# 00A-004.net
KiCad netlist of a schematic drawn in EAGLE
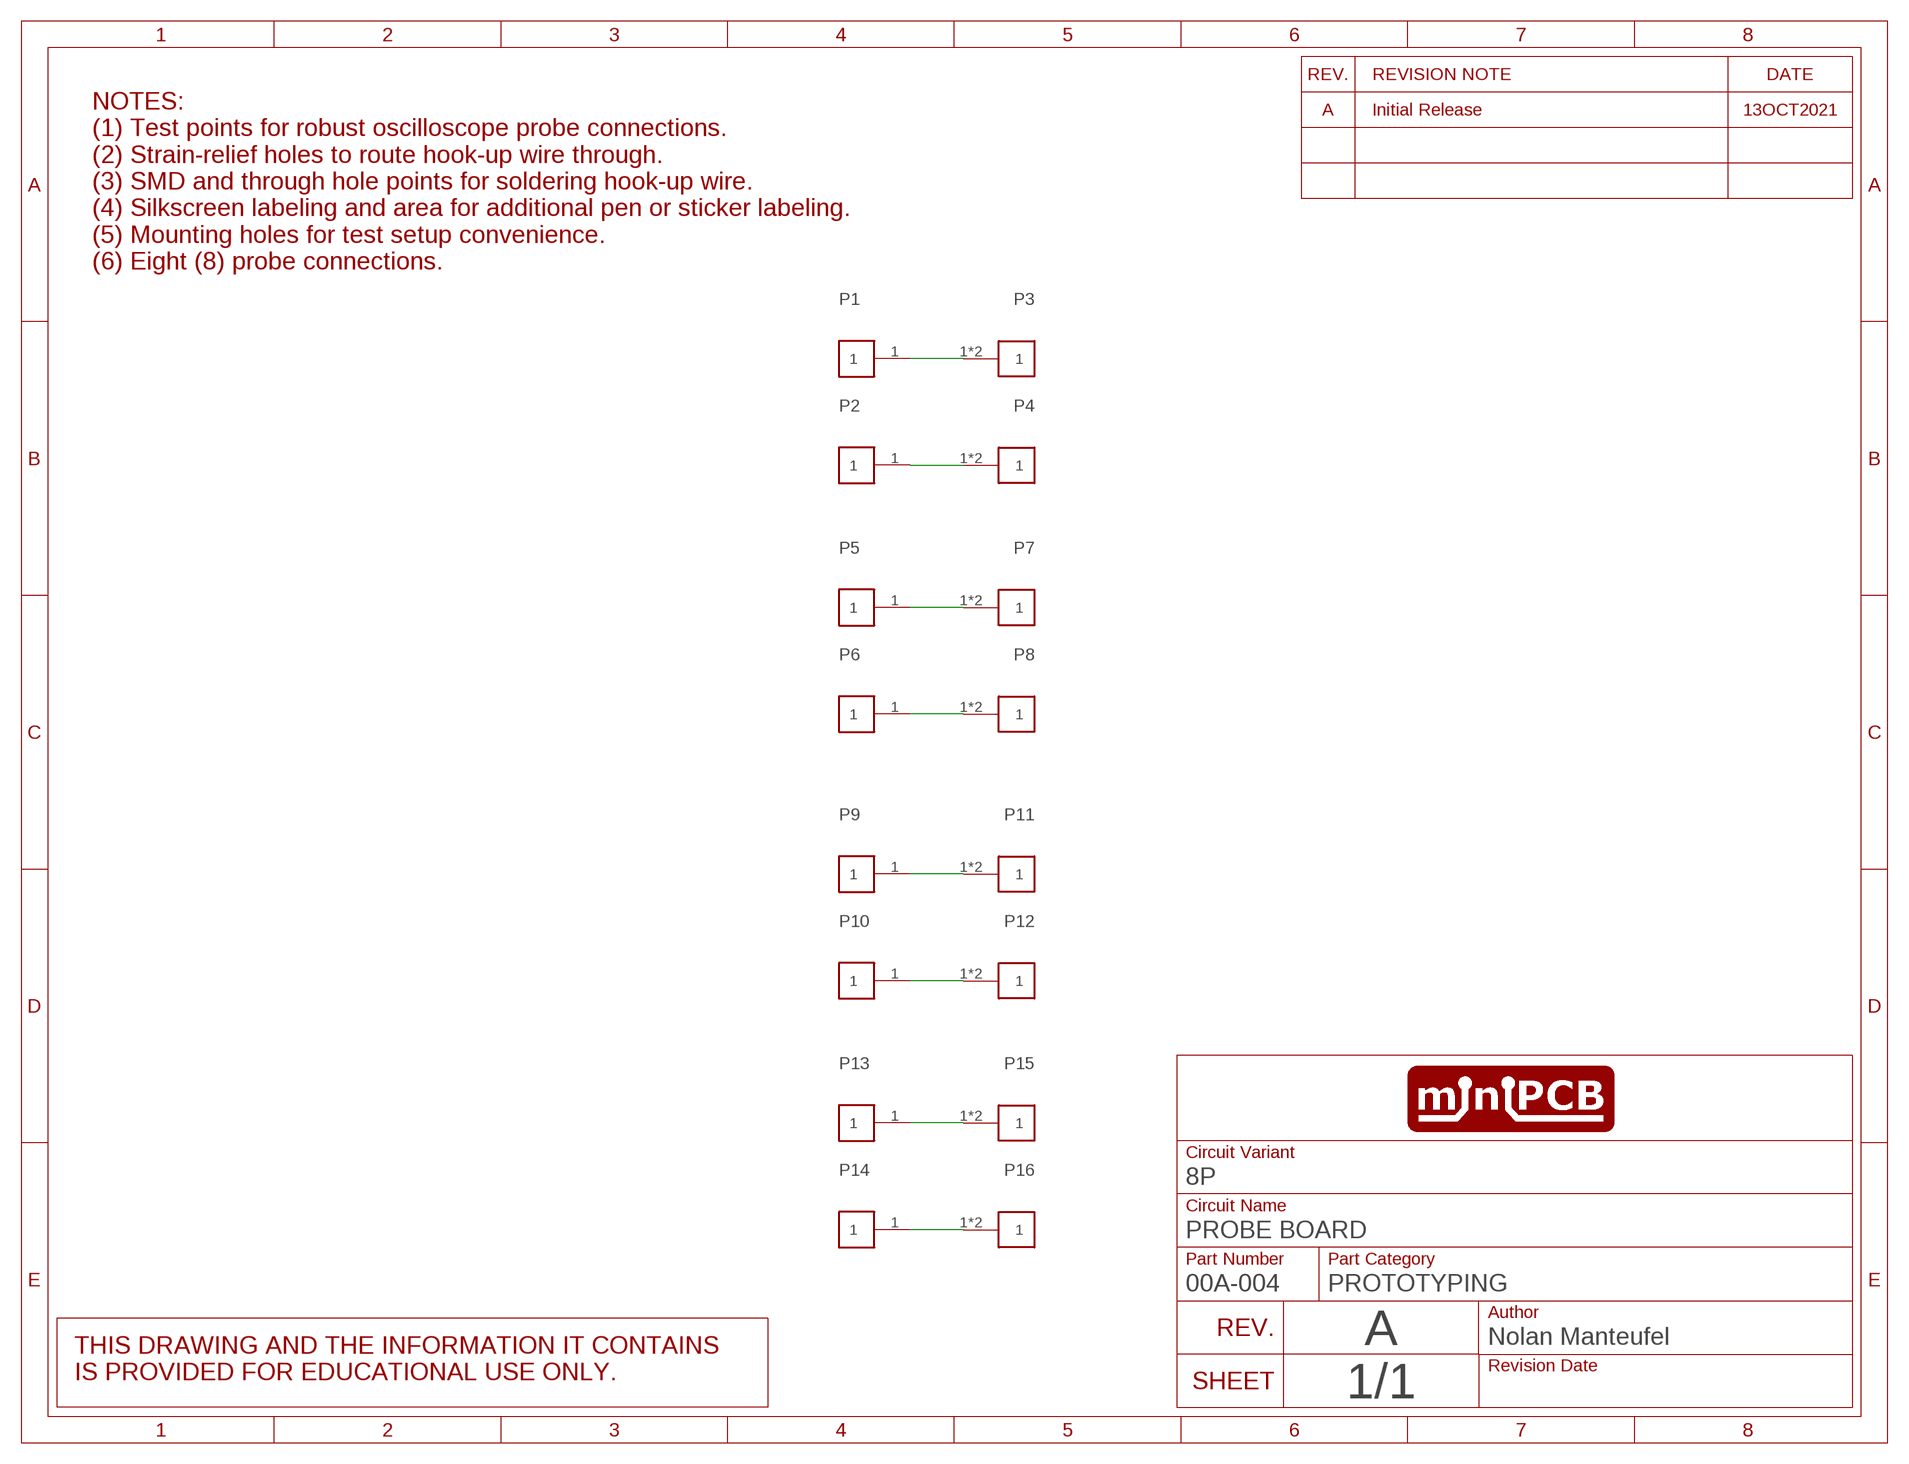
[diagram p0: schematic, sheet 1]

(export (version "E")
  (design (tool "Eeschema 10.0.6"))
  (components
    (comp (ref "P1")
      (value "PINS_1KE_5000")
      (footprint "eagle-import:PINS_1_TESTPOINT_KE5000")
      (libsource (lib "eagle-import") (part "PINS_1KE_5000"))
    )
    (comp (ref "P2")
      (value "PINS_1KE_5000")
      (footprint "eagle-import:PINS_1_TESTPOINT_KE5000")
      (libsource (lib "eagle-import") (part "PINS_1KE_5000"))
    )
    (comp (ref "P3")
      (value "PINS_124AWG")
      (footprint "eagle-import:PINS_1_1MM")
      (libsource (lib "eagle-import") (part "PINS_124AWG"))
    )
    (comp (ref "P4")
      (value "PINS_124AWG")
      (footprint "eagle-import:PINS_1_1MM")
      (libsource (lib "eagle-import") (part "PINS_124AWG"))
    )
    (comp (ref "P5")
      (value "PINS_1KE_5000")
      (footprint "eagle-import:PINS_1_TESTPOINT_KE5000")
      (libsource (lib "eagle-import") (part "PINS_1KE_5000"))
    )
    (comp (ref "P6")
      (value "PINS_1KE_5000")
      (footprint "eagle-import:PINS_1_TESTPOINT_KE5000")
      (libsource (lib "eagle-import") (part "PINS_1KE_5000"))
    )
    (comp (ref "P7")
      (value "PINS_124AWG")
      (footprint "eagle-import:PINS_1_1MM")
      (libsource (lib "eagle-import") (part "PINS_124AWG"))
    )
    (comp (ref "P8")
      (value "PINS_124AWG")
      (footprint "eagle-import:PINS_1_1MM")
      (libsource (lib "eagle-import") (part "PINS_124AWG"))
    )
    (comp (ref "P9")
      (value "PINS_1KE_5000")
      (footprint "eagle-import:PINS_1_TESTPOINT_KE5000")
      (libsource (lib "eagle-import") (part "PINS_1KE_5000"))
    )
    (comp (ref "P10")
      (value "PINS_1KE_5000")
      (footprint "eagle-import:PINS_1_TESTPOINT_KE5000")
      (libsource (lib "eagle-import") (part "PINS_1KE_5000"))
    )
    (comp (ref "P11")
      (value "PINS_124AWG")
      (footprint "eagle-import:PINS_1_1MM")
      (libsource (lib "eagle-import") (part "PINS_124AWG"))
    )
    (comp (ref "P12")
      (value "PINS_124AWG")
      (footprint "eagle-import:PINS_1_1MM")
      (libsource (lib "eagle-import") (part "PINS_124AWG"))
    )
    (comp (ref "P13")
      (value "PINS_1KE_5000")
      (footprint "eagle-import:PINS_1_TESTPOINT_KE5000")
      (libsource (lib "eagle-import") (part "PINS_1KE_5000"))
    )
    (comp (ref "P14")
      (value "PINS_1KE_5000")
      (footprint "eagle-import:PINS_1_TESTPOINT_KE5000")
      (libsource (lib "eagle-import") (part "PINS_1KE_5000"))
    )
    (comp (ref "P15")
      (value "PINS_124AWG")
      (footprint "eagle-import:PINS_1_1MM")
      (libsource (lib "eagle-import") (part "PINS_124AWG"))
    )
    (comp (ref "P16")
      (value "PINS_124AWG")
      (footprint "eagle-import:PINS_1_1MM")
      (libsource (lib "eagle-import") (part "PINS_124AWG"))
    )
  )
  (nets
    (net (code "1") (name "Net-(P1-Pad1)") (class "Default")
      (node (ref "P1") (pin "1") (pinfunction "1_1") (pintype "bidirectional"))
      (node (ref "P3") (pin "1") (pinfunction "1_1") (pintype "bidirectional"))
      (node (ref "P3") (pin "2") (pinfunction "1_2") (pintype "bidirectional"))
    )
    (net (code "2") (name "Net-(P2-Pad1)") (class "Default")
      (node (ref "P2") (pin "1") (pinfunction "1_1") (pintype "bidirectional"))
      (node (ref "P4") (pin "1") (pinfunction "1_1") (pintype "bidirectional"))
      (node (ref "P4") (pin "2") (pinfunction "1_2") (pintype "bidirectional"))
    )
    (net (code "3") (name "Net-(P5-Pad1)") (class "Default")
      (node (ref "P5") (pin "1") (pinfunction "1_1") (pintype "bidirectional"))
      (node (ref "P7") (pin "1") (pinfunction "1_1") (pintype "bidirectional"))
      (node (ref "P7") (pin "2") (pinfunction "1_2") (pintype "bidirectional"))
    )
    (net (code "4") (name "Net-(P6-Pad1)") (class "Default")
      (node (ref "P6") (pin "1") (pinfunction "1_1") (pintype "bidirectional"))
      (node (ref "P8") (pin "1") (pinfunction "1_1") (pintype "bidirectional"))
      (node (ref "P8") (pin "2") (pinfunction "1_2") (pintype "bidirectional"))
    )
    (net (code "5") (name "Net-(P10-Pad1)") (class "Default")
      (node (ref "P10") (pin "1") (pinfunction "1_1") (pintype "bidirectional"))
      (node (ref "P12") (pin "1") (pinfunction "1_1") (pintype "bidirectional"))
      (node (ref "P12") (pin "2") (pinfunction "1_2") (pintype "bidirectional"))
    )
    (net (code "6") (name "Net-(P11-1-Pad2)") (class "Default")
      (node (ref "P11") (pin "1") (pinfunction "1_1") (pintype "bidirectional"))
      (node (ref "P11") (pin "2") (pinfunction "1_2") (pintype "bidirectional"))
      (node (ref "P9") (pin "1") (pinfunction "1_1") (pintype "bidirectional"))
    )
    (net (code "7") (name "Net-(P13-Pad1)") (class "Default")
      (node (ref "P13") (pin "1") (pinfunction "1_1") (pintype "bidirectional"))
      (node (ref "P15") (pin "1") (pinfunction "1_1") (pintype "bidirectional"))
      (node (ref "P15") (pin "2") (pinfunction "1_2") (pintype "bidirectional"))
    )
    (net (code "8") (name "Net-(P14-Pad1)") (class "Default")
      (node (ref "P14") (pin "1") (pinfunction "1_1") (pintype "bidirectional"))
      (node (ref "P16") (pin "1") (pinfunction "1_1") (pintype "bidirectional"))
      (node (ref "P16") (pin "2") (pinfunction "1_2") (pintype "bidirectional"))
    )
  )
)
